# TAS5822.net
KiCad netlist of a schematic drawn in Altium Designer
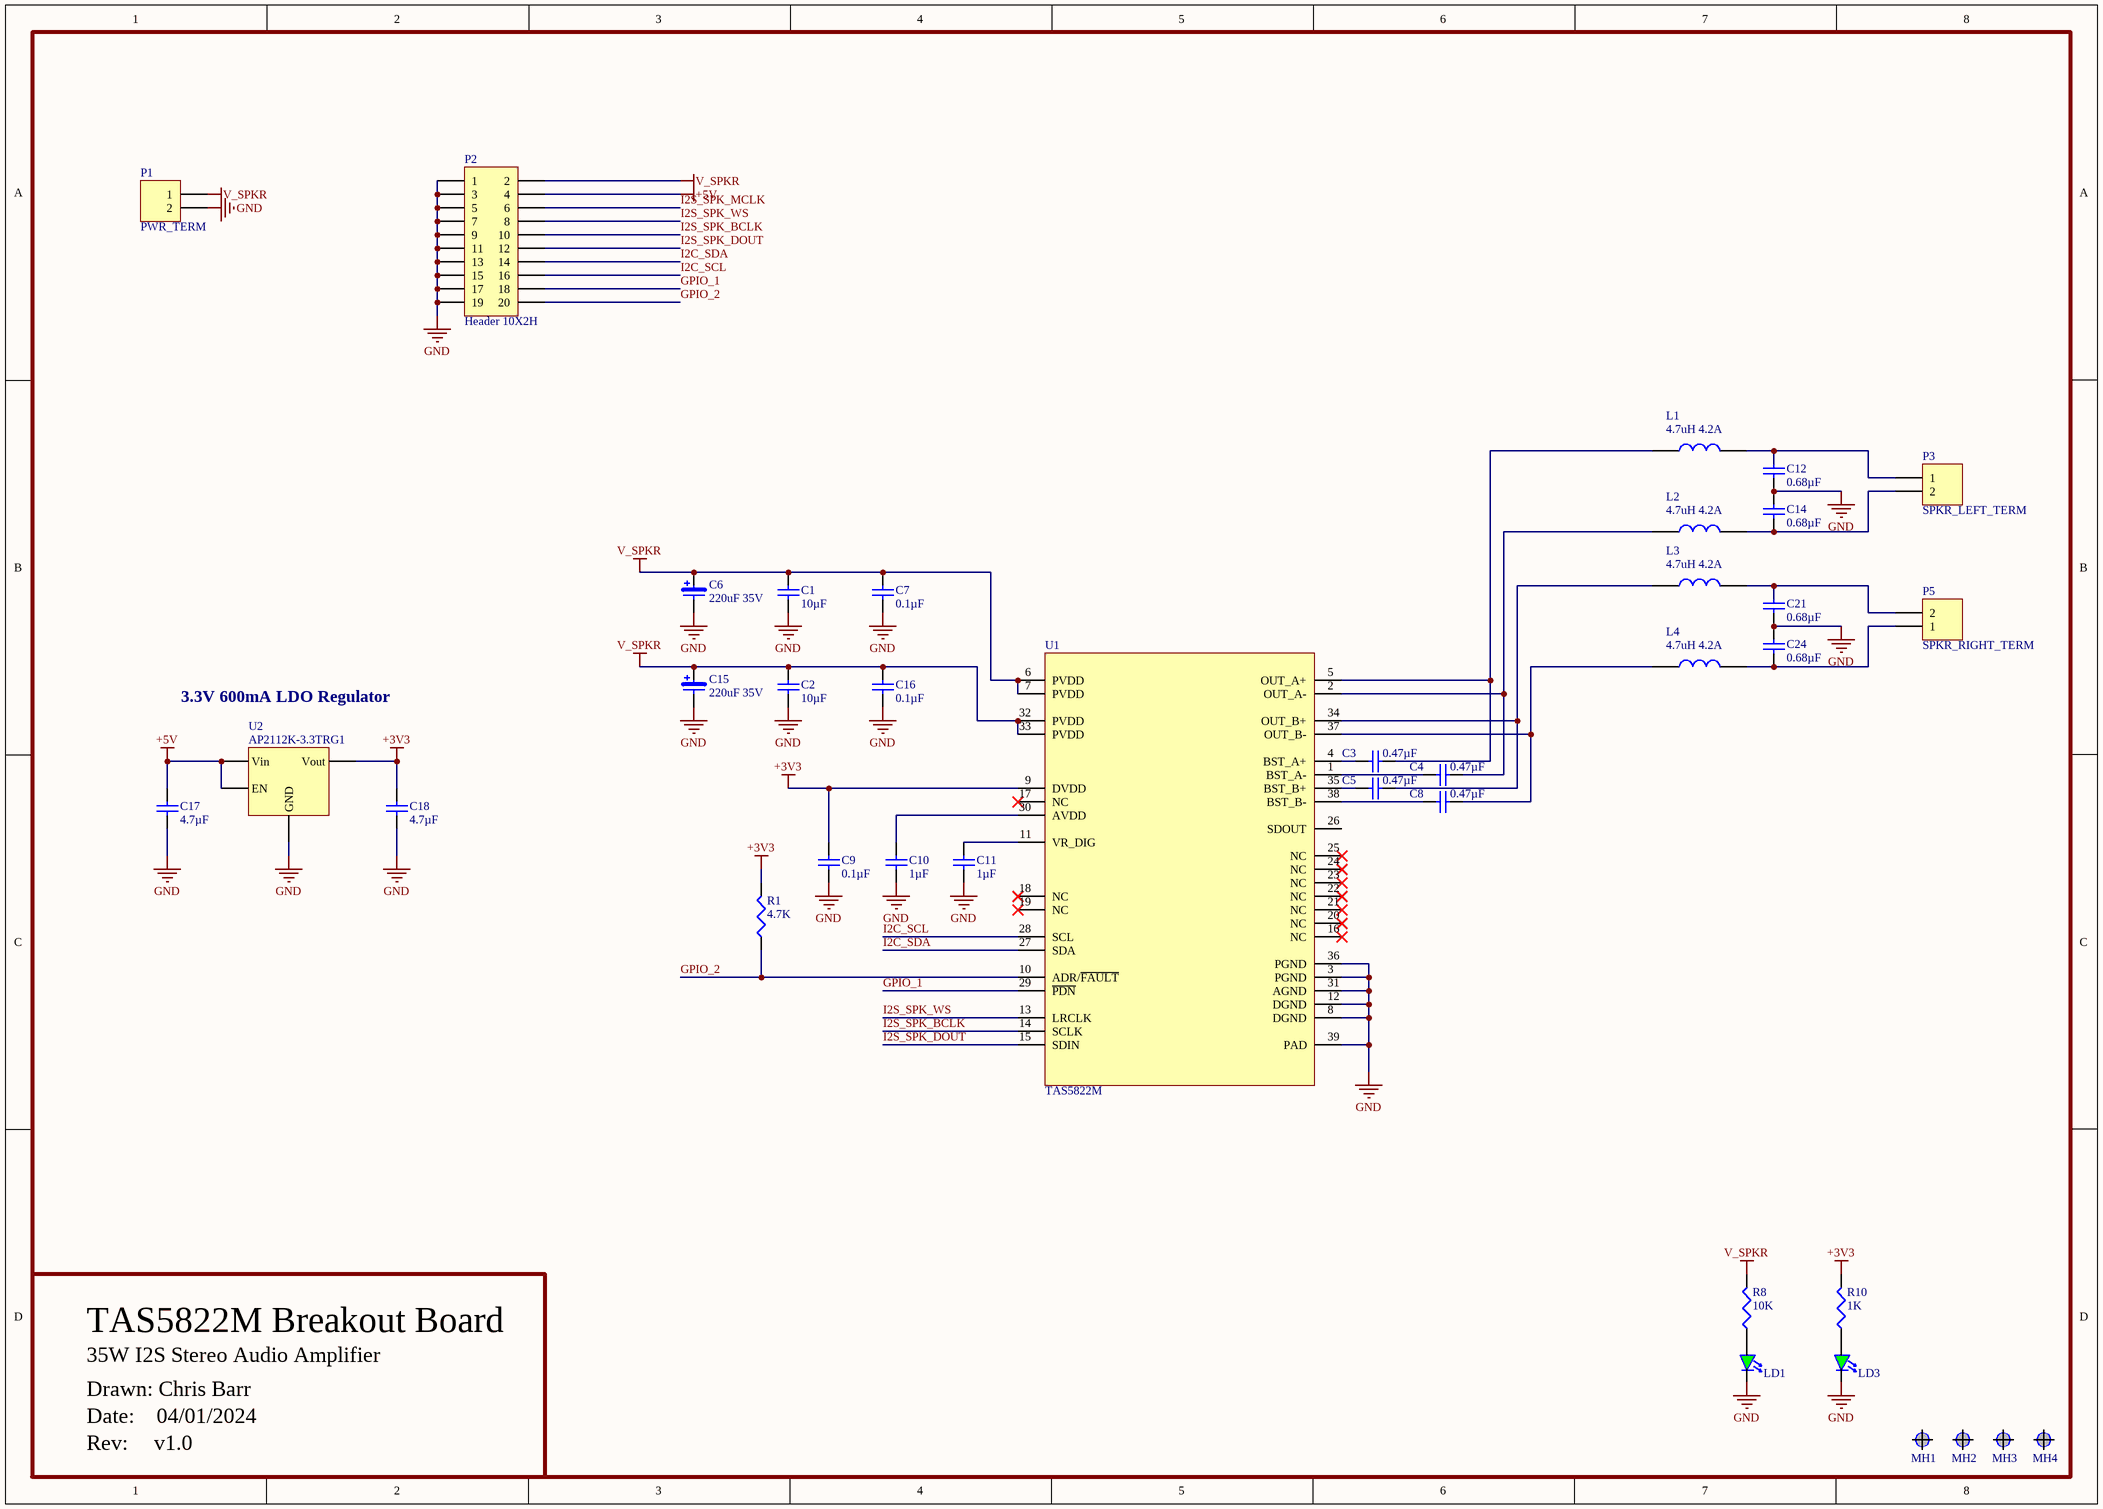
[diagram p0: TAS5822.SchDoc]

(export (version "E")
  (design (tool "Eeschema 10.0.6"))
  (components
    (comp (ref "C1")
      (value "10µF")
      (footprint "CAPC3216X100N")
      (description "CAP CER 10UF 35V X5R 1206")
      (fields (field (name "VOLTAGE") "35V") (field (name "TOLERANCE") "±20%"))
      (libsource (lib "Ceramic Cap DBLIB") (part "Capacitor"))
    )
    (comp (ref "C2")
      (value "10µF")
      (footprint "CAPC3216X100N")
      (description "CAP CER 10UF 35V X5R 1206")
      (fields (field (name "VOLTAGE") "35V") (field (name "TOLERANCE") "±20%"))
      (libsource (lib "Ceramic Cap DBLIB") (part "Capacitor"))
    )
    (comp (ref "C3")
      (value "0.47µF")
      (footprint "CAPC1608X90N")
      (description "CAP CER 0.47UF 35V X7R 0603")
      (fields (field (name "VOLTAGE") "35V") (field (name "TOLERANCE") "±10%"))
      (libsource (lib "Ceramic Cap DBLIB") (part "Capacitor"))
    )
    (comp (ref "C4")
      (value "0.47µF")
      (footprint "CAPC1608X90N")
      (description "CAP CER 0.47UF 35V X7R 0603")
      (fields (field (name "VOLTAGE") "35V") (field (name "TOLERANCE") "±10%"))
      (libsource (lib "Ceramic Cap DBLIB") (part "Capacitor"))
    )
    (comp (ref "C5")
      (value "0.47µF")
      (footprint "CAPC1608X90N")
      (description "CAP CER 0.47UF 35V X7R 0603")
      (fields (field (name "VOLTAGE") "35V") (field (name "TOLERANCE") "±10%"))
      (libsource (lib "Ceramic Cap DBLIB") (part "Capacitor"))
    )
    (comp (ref "C6")
      (value "220uF 35V")
      (footprint "CAPAE250P680X1220_VERT")
      (description "CAP ALUM 220UF 20% 35V RADIAL")
      (fields (field (name "Comment") "CapE-8.0-THT-220uF-35V") (field (name "PUBLISHER") "Altium Limited"))
      (libsource (lib "main_library") (part "CapE-8.0-THT-220uF-35V"))
    )
    (comp (ref "C7")
      (value "0.1µF")
      (footprint "CAPC1608X90N")
      (description "CAP CER 0.1UF 50V X7R 0603")
      (fields (field (name "VOLTAGE") "50V") (field (name "TOLERANCE") "±10%"))
      (libsource (lib "Ceramic Cap DBLIB") (part "Capacitor"))
    )
    (comp (ref "C8")
      (value "0.47µF")
      (footprint "CAPC1608X90N")
      (description "CAP CER 0.47UF 35V X7R 0603")
      (fields (field (name "VOLTAGE") "35V") (field (name "TOLERANCE") "±10%"))
      (libsource (lib "Ceramic Cap DBLIB") (part "Capacitor"))
    )
    (comp (ref "C9")
      (value "0.1µF")
      (footprint "CAPC1608X90N")
      (description "CAP CER 0.1UF 50V X7R 0603")
      (fields (field (name "VOLTAGE") "50V") (field (name "TOLERANCE") "±10%"))
      (libsource (lib "Ceramic Cap DBLIB") (part "Capacitor"))
    )
    (comp (ref "C10")
      (value "1µF")
      (footprint "CAPC1608X90N")
      (description "CAP CER 1UF 35V X5R 0603")
      (fields (field (name "VOLTAGE") "35V") (field (name "TOLERANCE") "±10%"))
      (libsource (lib "Ceramic Cap DBLIB") (part "Capacitor"))
    )
    (comp (ref "C11")
      (value "1µF")
      (footprint "CAPC1608X90N")
      (description "CAP CER 1UF 35V X5R 0603")
      (fields (field (name "VOLTAGE") "35V") (field (name "TOLERANCE") "±10%"))
      (libsource (lib "Ceramic Cap DBLIB") (part "Capacitor"))
    )
    (comp (ref "C12")
      (value "0.68µF")
      (footprint "CAPC3216X100N")
      (description "CAP CER 0.68UF 100V X7R 1206")
      (fields (field (name "VOLTAGE") "100V") (field (name "TOLERANCE") "±10%"))
      (libsource (lib "Ceramic Cap DBLIB") (part "Capacitor"))
    )
    (comp (ref "C14")
      (value "0.68µF")
      (footprint "CAPC3216X100N")
      (description "CAP CER 0.68UF 100V X7R 1206")
      (fields (field (name "VOLTAGE") "100V") (field (name "TOLERANCE") "±10%"))
      (libsource (lib "Ceramic Cap DBLIB") (part "Capacitor"))
    )
    (comp (ref "C15")
      (value "220uF 35V")
      (footprint "CAPAE250P680X1220_VERT")
      (description "CAP ALUM 220UF 20% 35V RADIAL")
      (fields (field (name "Comment") "CapE-8.0-THT-220uF-35V") (field (name "PUBLISHER") "Altium Limited"))
      (libsource (lib "main_library") (part "CapE-8.0-THT-220uF-35V"))
    )
    (comp (ref "C16")
      (value "0.1µF")
      (footprint "CAPC1608X90N")
      (description "CAP CER 0.1UF 50V X7R 0603")
      (fields (field (name "VOLTAGE") "50V") (field (name "TOLERANCE") "±10%"))
      (libsource (lib "Ceramic Cap DBLIB") (part "Capacitor"))
    )
    (comp (ref "C17")
      (value "4.7µF")
      (footprint "CAPC1608X90N")
      (description "CAP CER 4.7UF 16V X5R 0603")
      (fields (field (name "VOLTAGE") "16V") (field (name "TOLERANCE") "±10%"))
      (libsource (lib "Ceramic Cap DBLIB") (part "Capacitor"))
    )
    (comp (ref "C18")
      (value "4.7µF")
      (footprint "CAPC1608X90N")
      (description "CAP CER 4.7UF 16V X5R 0603")
      (fields (field (name "VOLTAGE") "16V") (field (name "TOLERANCE") "±10%"))
      (libsource (lib "Ceramic Cap DBLIB") (part "Capacitor"))
    )
    (comp (ref "C21")
      (value "0.68µF")
      (footprint "CAPC3216X100N")
      (description "CAP CER 0.68UF 100V X7R 1206")
      (fields (field (name "VOLTAGE") "100V") (field (name "TOLERANCE") "±10%"))
      (libsource (lib "Ceramic Cap DBLIB") (part "Capacitor"))
    )
    (comp (ref "C24")
      (value "0.68µF")
      (footprint "CAPC3216X100N")
      (description "CAP CER 0.68UF 100V X7R 1206")
      (fields (field (name "VOLTAGE") "100V") (field (name "TOLERANCE") "±10%"))
      (libsource (lib "Ceramic Cap DBLIB") (part "Capacitor"))
    )
    (comp (ref "L1")
      (value "4.7uH 4.2A")
      (footprint "SRN6045TA SMD Inductor")
      (description "FIXED IND 4.7UH 4.2A 35 MOHM SMD")
      (fields (field (name "Comment") "Inductor SMD 10uH 2.4A") (field (name "PUBLISHER") "Altium Limited"))
      (libsource (lib "main_library") (part "Inductor SMD 33uH 2.5A"))
    )
    (comp (ref "L2")
      (value "4.7uH 4.2A")
      (footprint "SRN6045TA SMD Inductor")
      (description "FIXED IND 4.7UH 4.2A 35 MOHM SMD")
      (fields (field (name "Comment") "Inductor SMD 10uH 2.4A") (field (name "PUBLISHER") "Altium Limited"))
      (libsource (lib "main_library") (part "Inductor SMD 33uH 2.5A"))
    )
    (comp (ref "L3")
      (value "4.7uH 4.2A")
      (footprint "SRN6045TA SMD Inductor")
      (description "FIXED IND 4.7UH 4.2A 35 MOHM SMD")
      (fields (field (name "Comment") "Inductor SMD 10uH 2.4A") (field (name "PUBLISHER") "Altium Limited"))
      (libsource (lib "main_library") (part "Inductor SMD 33uH 2.5A"))
    )
    (comp (ref "L4")
      (value "4.7uH 4.2A")
      (footprint "SRN6045TA SMD Inductor")
      (description "FIXED IND 4.7UH 4.2A 35 MOHM SMD")
      (fields (field (name "Comment") "Inductor SMD 10uH 2.4A") (field (name "PUBLISHER") "Altium Limited"))
      (libsource (lib "main_library") (part "Inductor SMD 33uH 2.5A"))
    )
    (comp (ref "LD1")
      (value "LEDG  0603")
      (footprint "LED 1608-0603")
      (description "LED GREEN CLEAR CHIP SMD 0603")
      (libsource (lib "main_library") (part "LEDG  0603"))
    )
    (comp (ref "LD3")
      (value "LEDG  0603")
      (footprint "LED 1608-0603")
      (description "LED GREEN CLEAR CHIP SMD 0603")
      (libsource (lib "main_library") (part "LEDG  0603"))
    )
    (comp (ref "MH1")
      (value "Screw Hole")
      (footprint "M3-Hole-2")
      (libsource (lib "main_library") (part "Screw Hole"))
    )
    (comp (ref "MH2")
      (value "Screw Hole")
      (footprint "M3-Hole-2")
      (libsource (lib "main_library") (part "Screw Hole"))
    )
    (comp (ref "MH3")
      (value "Screw Hole")
      (footprint "M3-Hole-2")
      (libsource (lib "main_library") (part "Screw Hole"))
    )
    (comp (ref "MH4")
      (value "Screw Hole")
      (footprint "M3-Hole-2")
      (libsource (lib "main_library") (part "Screw Hole"))
    )
    (comp (ref "P1")
      (value "PWR_TERM")
      (footprint "TERM2 3.5mm")
      (description "Screw Terminal 3.5mm 2-Way")
      (libsource (lib "") (part "ScrewTerminal-3.5mm-2Way_1"))
    )
    (comp (ref "P2")
      (value "Header 10X2H")
      (footprint "HDR2X10H")
      (description "Header, 10-Pin, Dual row, Right Angle")
      (fields (field (name "PUBLISHER") "Altium Limited"))
      (libsource (lib "Miscellaneous Connectors") (part "Header 10X2H"))
    )
    (comp (ref "P3")
      (value "SPKR_LEFT_TERM")
      (footprint "TERM2 3.5mm")
      (description "Screw Terminal 3.5mm 2-Way")
      (libsource (lib "") (part "ScrewTerminal-3.5mm-2Way_2"))
    )
    (comp (ref "P5")
      (value "SPKR_RIGHT_TERM")
      (footprint "TERM2 3.5mm")
      (description "Screw Terminal 3.5mm 2-Way")
      (libsource (lib "main_library") (part "ScrewTerminal-3.5mm-2Way"))
    )
    (comp (ref "R1")
      (value "4.7K")
      (footprint "RES 1608-0603")
      (description "RES SMD 4.7K OHM 1% 1/10W 0603")
      (fields
        (field (name "TOLERANCE") "±1%")
        (field (name "Comment") "Resistor")
        (field (name "PUBLISHER") "Altium Limited")
      )
      (libsource (lib "Database_Libs1") (part "Resistor"))
    )
    (comp (ref "R8")
      (value "10K")
      (footprint "RES 1608-0603")
      (description "RES SMD 10K OHM 1% 1/10W 0603")
      (fields
        (field (name "TOLERANCE") "±1%")
        (field (name "Comment") "Resistor")
        (field (name "PUBLISHER") "Altium Limited")
      )
      (libsource (lib "Database_Libs1") (part "Resistor"))
    )
    (comp (ref "R10")
      (value "1K")
      (footprint "RES 1608-0603")
      (description "RES SMD 1K OHM 1% 1/10W 0603")
      (fields
        (field (name "TOLERANCE") "±1%")
        (field (name "Comment") "Resistor")
        (field (name "PUBLISHER") "Altium Limited")
      )
      (libsource (lib "Database_Libs1") (part "Resistor"))
    )
    (comp (ref "U1")
      (value "TAS5822M")
      (footprint "TSSOP50P640X120_HS-39N")
      (description "35-W, INDUCTOR-LESS, DIGITAL INP")
      (libsource (lib "main_library") (part "IC - DAC, I2S Amplifier - TAS5822M"))
    )
    (comp (ref "U2")
      (value "AP2112K-3.3TRG1")
      (footprint "SOT23-5")
      (description "IC REG LINEAR 3.3V 600MA SOT25")
      (libsource (lib "picoprint_library") (part "Regulator - AP2112K 3.3V Linear Regulator"))
    )
  )
  (nets
    (net (code "1") (name "+3V3") (class "Default")
      (node (ref "C18") (pin "2") (pinfunction "2_2") (pintype "passive"))
      (node (ref "C9") (pin "2") (pinfunction "2_2") (pintype "passive"))
      (node (ref "R1") (pin "2") (pinfunction "2_2") (pintype "passive"))
      (node (ref "R10") (pin "2") (pinfunction "2_2") (pintype "passive"))
      (node (ref "U1") (pin "9") (pinfunction "DVDD_9") (pintype "passive"))
      (node (ref "U2") (pin "5") (pinfunction "Vout_5") (pintype "passive"))
    )
    (net (code "2") (name "+5V") (class "Default")
      (node (ref "C17") (pin "2") (pinfunction "2_2") (pintype "passive"))
      (node (ref "P2") (pin "4") (pinfunction "4_4") (pintype "passive"))
      (node (ref "U2") (pin "1") (pinfunction "Vin_1") (pintype "passive"))
      (node (ref "U2") (pin "3") (pinfunction "EN_3") (pintype "passive"))
    )
    (net (code "3") (name "/GPIO_1") (class "Default")
      (node (ref "P2") (pin "18") (pinfunction "18_18") (pintype "passive"))
      (node (ref "U1") (pin "29") (pinfunction "~{PDN}_29") (pintype "passive"))
    )
    (net (code "4") (name "/GPIO_2") (class "Default")
      (node (ref "P2") (pin "20") (pinfunction "20_20") (pintype "passive"))
      (node (ref "R1") (pin "1") (pinfunction "1_1") (pintype "passive"))
      (node (ref "U1") (pin "10") (pinfunction "ADR/~{FAULT}_10") (pintype "passive"))
    )
    (net (code "5") (name "/I2C_SCL") (class "Default")
      (node (ref "P2") (pin "16") (pinfunction "16_16") (pintype "passive"))
      (node (ref "U1") (pin "28") (pinfunction "SCL_28") (pintype "passive"))
    )
    (net (code "6") (name "/I2C_SDA") (class "Default")
      (node (ref "P2") (pin "14") (pinfunction "14_14") (pintype "passive"))
      (node (ref "U1") (pin "27") (pinfunction "SDA_27") (pintype "passive"))
    )
    (net (code "7") (name "/I2S_SPK_BCLK") (class "Default")
      (node (ref "P2") (pin "10") (pinfunction "10_10") (pintype "passive"))
      (node (ref "U1") (pin "14") (pinfunction "SCLK_14") (pintype "passive"))
    )
    (net (code "8") (name "/I2S_SPK_DOUT") (class "Default")
      (node (ref "P2") (pin "12") (pinfunction "12_12") (pintype "passive"))
      (node (ref "U1") (pin "15") (pinfunction "SDIN_15") (pintype "passive"))
    )
    (net (code "9") (name "/I2S_SPK_MCLK") (class "Default")
      (node (ref "P2") (pin "6") (pinfunction "6_6") (pintype "passive"))
    )
    (net (code "10") (name "/I2S_SPK_WS") (class "Default")
      (node (ref "P2") (pin "8") (pinfunction "8_8") (pintype "passive"))
      (node (ref "U1") (pin "13") (pinfunction "LRCLK_13") (pintype "passive"))
    )
    (net (code "11") (name "GND") (class "Default")
      (node (ref "C1") (pin "1") (pinfunction "1_1") (pintype "passive"))
      (node (ref "C10") (pin "1") (pinfunction "1_1") (pintype "passive"))
      (node (ref "C11") (pin "1") (pinfunction "1_1") (pintype "passive"))
      (node (ref "C12") (pin "1") (pinfunction "1_1") (pintype "passive"))
      (node (ref "C14") (pin "2") (pinfunction "2_2") (pintype "passive"))
      (node (ref "C15") (pin "2") (pinfunction "2_2") (pintype "passive"))
      (node (ref "C16") (pin "1") (pinfunction "1_1") (pintype "passive"))
      (node (ref "C17") (pin "1") (pinfunction "1_1") (pintype "passive"))
      (node (ref "C18") (pin "1") (pinfunction "1_1") (pintype "passive"))
      (node (ref "C2") (pin "1") (pinfunction "1_1") (pintype "passive"))
      (node (ref "C21") (pin "1") (pinfunction "1_1") (pintype "passive"))
      (node (ref "C24") (pin "2") (pinfunction "2_2") (pintype "passive"))
      (node (ref "C6") (pin "2") (pinfunction "2_2") (pintype "passive"))
      (node (ref "C7") (pin "1") (pinfunction "1_1") (pintype "passive"))
      (node (ref "C9") (pin "1") (pinfunction "1_1") (pintype "passive"))
      (node (ref "LD1") (pin "2") (pinfunction "K_2") (pintype "passive"))
      (node (ref "LD3") (pin "2") (pinfunction "K_2") (pintype "passive"))
      (node (ref "P1") (pin "2") (pinfunction "2_2") (pintype "power_in"))
      (node (ref "P2") (pin "1") (pinfunction "1_1") (pintype "passive"))
      (node (ref "P2") (pin "11") (pinfunction "11_11") (pintype "passive"))
      (node (ref "P2") (pin "13") (pinfunction "13_13") (pintype "passive"))
      (node (ref "P2") (pin "15") (pinfunction "15_15") (pintype "passive"))
      (node (ref "P2") (pin "17") (pinfunction "17_17") (pintype "passive"))
      (node (ref "P2") (pin "19") (pinfunction "19_19") (pintype "passive"))
      (node (ref "P2") (pin "3") (pinfunction "3_3") (pintype "passive"))
      (node (ref "P2") (pin "5") (pinfunction "5_5") (pintype "passive"))
      (node (ref "P2") (pin "7") (pinfunction "7_7") (pintype "passive"))
      (node (ref "P2") (pin "9") (pinfunction "9_9") (pintype "passive"))
      (node (ref "U1") (pin "12") (pinfunction "DGND_12") (pintype "passive"))
      (node (ref "U1") (pin "3") (pinfunction "PGND_3") (pintype "passive"))
      (node (ref "U1") (pin "31") (pinfunction "AGND_31") (pintype "passive"))
      (node (ref "U1") (pin "36") (pinfunction "PGND_36") (pintype "passive"))
      (node (ref "U1") (pin "39") (pinfunction "PAD_39") (pintype "passive"))
      (node (ref "U1") (pin "8") (pinfunction "DGND_8") (pintype "passive"))
      (node (ref "U2") (pin "2") (pinfunction "GND_2") (pintype "passive"))
    )
    (net (code "12") (name "Net-(C12-Pad2)") (class "Default")
      (node (ref "C12") (pin "2") (pinfunction "2_2") (pintype "passive"))
      (node (ref "L1") (pin "2") (pinfunction "2_2") (pintype "passive"))
      (node (ref "P3") (pin "1") (pinfunction "1_1") (pintype "power_in"))
    )
    (net (code "13") (name "Net-(C14-Pad1)") (class "Default")
      (node (ref "C14") (pin "1") (pinfunction "1_1") (pintype "passive"))
      (node (ref "L2") (pin "2") (pinfunction "2_2") (pintype "passive"))
      (node (ref "P3") (pin "2") (pinfunction "2_2") (pintype "power_in"))
    )
    (net (code "14") (name "Net-(C21-Pad2)") (class "Default")
      (node (ref "C21") (pin "2") (pinfunction "2_2") (pintype "passive"))
      (node (ref "L3") (pin "2") (pinfunction "2_2") (pintype "passive"))
      (node (ref "P5") (pin "2") (pinfunction "2_2") (pintype "power_in"))
    )
    (net (code "15") (name "Net-(C24-Pad1)") (class "Default")
      (node (ref "C24") (pin "1") (pinfunction "1_1") (pintype "passive"))
      (node (ref "L4") (pin "2") (pinfunction "2_2") (pintype "passive"))
      (node (ref "P5") (pin "1") (pinfunction "1_1") (pintype "power_in"))
    )
    (net (code "16") (name "Net-(LD1-A)") (class "Default")
      (node (ref "LD1") (pin "1") (pinfunction "A_1") (pintype "passive"))
      (node (ref "R8") (pin "1") (pinfunction "1_1") (pintype "passive"))
    )
    (net (code "17") (name "Net-(LD3-A)") (class "Default")
      (node (ref "LD3") (pin "1") (pinfunction "A_1") (pintype "passive"))
      (node (ref "R10") (pin "1") (pinfunction "1_1") (pintype "passive"))
    )
    (net (code "18") (name "Net-(U1-AVDD)") (class "Default")
      (node (ref "C10") (pin "2") (pinfunction "2_2") (pintype "passive"))
      (node (ref "U1") (pin "30") (pinfunction "AVDD_30") (pintype "passive"))
    )
    (net (code "19") (name "Net-(U1-BST_A+)") (class "Default")
      (node (ref "C3") (pin "1") (pinfunction "1_1") (pintype "passive"))
      (node (ref "U1") (pin "4") (pinfunction "BST_A+_4") (pintype "passive"))
    )
    (net (code "20") (name "Net-(U1-BST_A-)") (class "Default")
      (node (ref "C4") (pin "1") (pinfunction "1_1") (pintype "passive"))
      (node (ref "U1") (pin "1") (pinfunction "BST_A-_1") (pintype "passive"))
    )
    (net (code "21") (name "Net-(U1-BST_B+)") (class "Default")
      (node (ref "C5") (pin "1") (pinfunction "1_1") (pintype "passive"))
      (node (ref "U1") (pin "35") (pinfunction "BST_B+_35") (pintype "passive"))
    )
    (net (code "22") (name "Net-(U1-BST_B-)") (class "Default")
      (node (ref "C8") (pin "1") (pinfunction "1_1") (pintype "passive"))
      (node (ref "U1") (pin "38") (pinfunction "BST_B-_38") (pintype "passive"))
    )
    (net (code "23") (name "Net-(U1-OUT_A+)") (class "Default")
      (node (ref "C3") (pin "2") (pinfunction "2_2") (pintype "passive"))
      (node (ref "L1") (pin "1") (pinfunction "1_1") (pintype "passive"))
      (node (ref "U1") (pin "5") (pinfunction "OUT_A+_5") (pintype "passive"))
    )
    (net (code "24") (name "Net-(U1-OUT_A-)") (class "Default")
      (node (ref "C4") (pin "2") (pinfunction "2_2") (pintype "passive"))
      (node (ref "L2") (pin "1") (pinfunction "1_1") (pintype "passive"))
      (node (ref "U1") (pin "2") (pinfunction "OUT_A-_2") (pintype "passive"))
    )
    (net (code "25") (name "Net-(U1-OUT_B+)") (class "Default")
      (node (ref "C5") (pin "2") (pinfunction "2_2") (pintype "passive"))
      (node (ref "L3") (pin "1") (pinfunction "1_1") (pintype "passive"))
      (node (ref "U1") (pin "34") (pinfunction "OUT_B+_34") (pintype "passive"))
    )
    (net (code "26") (name "Net-(U1-OUT_B-)") (class "Default")
      (node (ref "C8") (pin "2") (pinfunction "2_2") (pintype "passive"))
      (node (ref "L4") (pin "1") (pinfunction "1_1") (pintype "passive"))
      (node (ref "U1") (pin "37") (pinfunction "OUT_B-_37") (pintype "passive"))
    )
    (net (code "27") (name "Net-(U1-VR_DIG)") (class "Default")
      (node (ref "C11") (pin "2") (pinfunction "2_2") (pintype "passive"))
      (node (ref "U1") (pin "11") (pinfunction "VR_DIG_11") (pintype "passive"))
    )
    (net (code "28") (name "V_SPKR") (class "Default")
      (node (ref "C1") (pin "2") (pinfunction "2_2") (pintype "passive"))
      (node (ref "C15") (pin "1") (pinfunction "1_1") (pintype "passive"))
      (node (ref "C16") (pin "2") (pinfunction "2_2") (pintype "passive"))
      (node (ref "C2") (pin "2") (pinfunction "2_2") (pintype "passive"))
      (node (ref "C6") (pin "1") (pinfunction "1_1") (pintype "passive"))
      (node (ref "C7") (pin "2") (pinfunction "2_2") (pintype "passive"))
      (node (ref "P1") (pin "1") (pinfunction "1_1") (pintype "power_in"))
      (node (ref "P2") (pin "2") (pinfunction "2_2") (pintype "passive"))
      (node (ref "R8") (pin "2") (pinfunction "2_2") (pintype "passive"))
      (node (ref "U1") (pin "32") (pinfunction "PVDD_32") (pintype "passive"))
      (node (ref "U1") (pin "33") (pinfunction "PVDD_33") (pintype "passive"))
      (node (ref "U1") (pin "6") (pinfunction "PVDD_6") (pintype "passive"))
      (node (ref "U1") (pin "7") (pinfunction "PVDD_7") (pintype "passive"))
    )
    (net (code "29") (name "unconnected-(MH1-0-PadM3)") (class "Default")
      (node (ref "MH1") (pin "M3") (pinfunction "0_M3") (pintype "passive"))
    )
    (net (code "30") (name "unconnected-(MH2-0-PadM3)") (class "Default")
      (node (ref "MH2") (pin "M3") (pinfunction "0_M3") (pintype "passive"))
    )
    (net (code "31") (name "unconnected-(MH3-0-PadM3)") (class "Default")
      (node (ref "MH3") (pin "M3") (pinfunction "0_M3") (pintype "passive"))
    )
    (net (code "32") (name "unconnected-(MH4-0-PadM3)") (class "Default")
      (node (ref "MH4") (pin "M3") (pinfunction "0_M3") (pintype "passive"))
    )
    (net (code "33") (name "unconnected-(U1-NC-Pad16)") (class "Default")
      (node (ref "U1") (pin "16") (pinfunction "NC_16") (pintype "passive+no_connect"))
    )
    (net (code "34") (name "unconnected-(U1-NC-Pad17)") (class "Default")
      (node (ref "U1") (pin "17") (pinfunction "NC_17") (pintype "passive+no_connect"))
    )
    (net (code "35") (name "unconnected-(U1-NC-Pad18)") (class "Default")
      (node (ref "U1") (pin "18") (pinfunction "NC_18") (pintype "passive+no_connect"))
    )
    (net (code "36") (name "unconnected-(U1-NC-Pad19)") (class "Default")
      (node (ref "U1") (pin "19") (pinfunction "NC_19") (pintype "passive+no_connect"))
    )
    (net (code "37") (name "unconnected-(U1-NC-Pad20)") (class "Default")
      (node (ref "U1") (pin "20") (pinfunction "NC_20") (pintype "passive+no_connect"))
    )
    (net (code "38") (name "unconnected-(U1-NC-Pad21)") (class "Default")
      (node (ref "U1") (pin "21") (pinfunction "NC_21") (pintype "passive+no_connect"))
    )
    (net (code "39") (name "unconnected-(U1-NC-Pad22)") (class "Default")
      (node (ref "U1") (pin "22") (pinfunction "NC_22") (pintype "passive+no_connect"))
    )
    (net (code "40") (name "unconnected-(U1-NC-Pad23)") (class "Default")
      (node (ref "U1") (pin "23") (pinfunction "NC_23") (pintype "passive+no_connect"))
    )
    (net (code "41") (name "unconnected-(U1-NC-Pad24)") (class "Default")
      (node (ref "U1") (pin "24") (pinfunction "NC_24") (pintype "passive+no_connect"))
    )
    (net (code "42") (name "unconnected-(U1-NC-Pad25)") (class "Default")
      (node (ref "U1") (pin "25") (pinfunction "NC_25") (pintype "passive+no_connect"))
    )
    (net (code "43") (name "unconnected-(U1-SDOUT-Pad26)") (class "Default")
      (node (ref "U1") (pin "26") (pinfunction "SDOUT_26") (pintype "passive"))
    )
  )
)
